# BMS_Master_RevB3.net
KiCad netlist of a schematic drawn in EAGLE
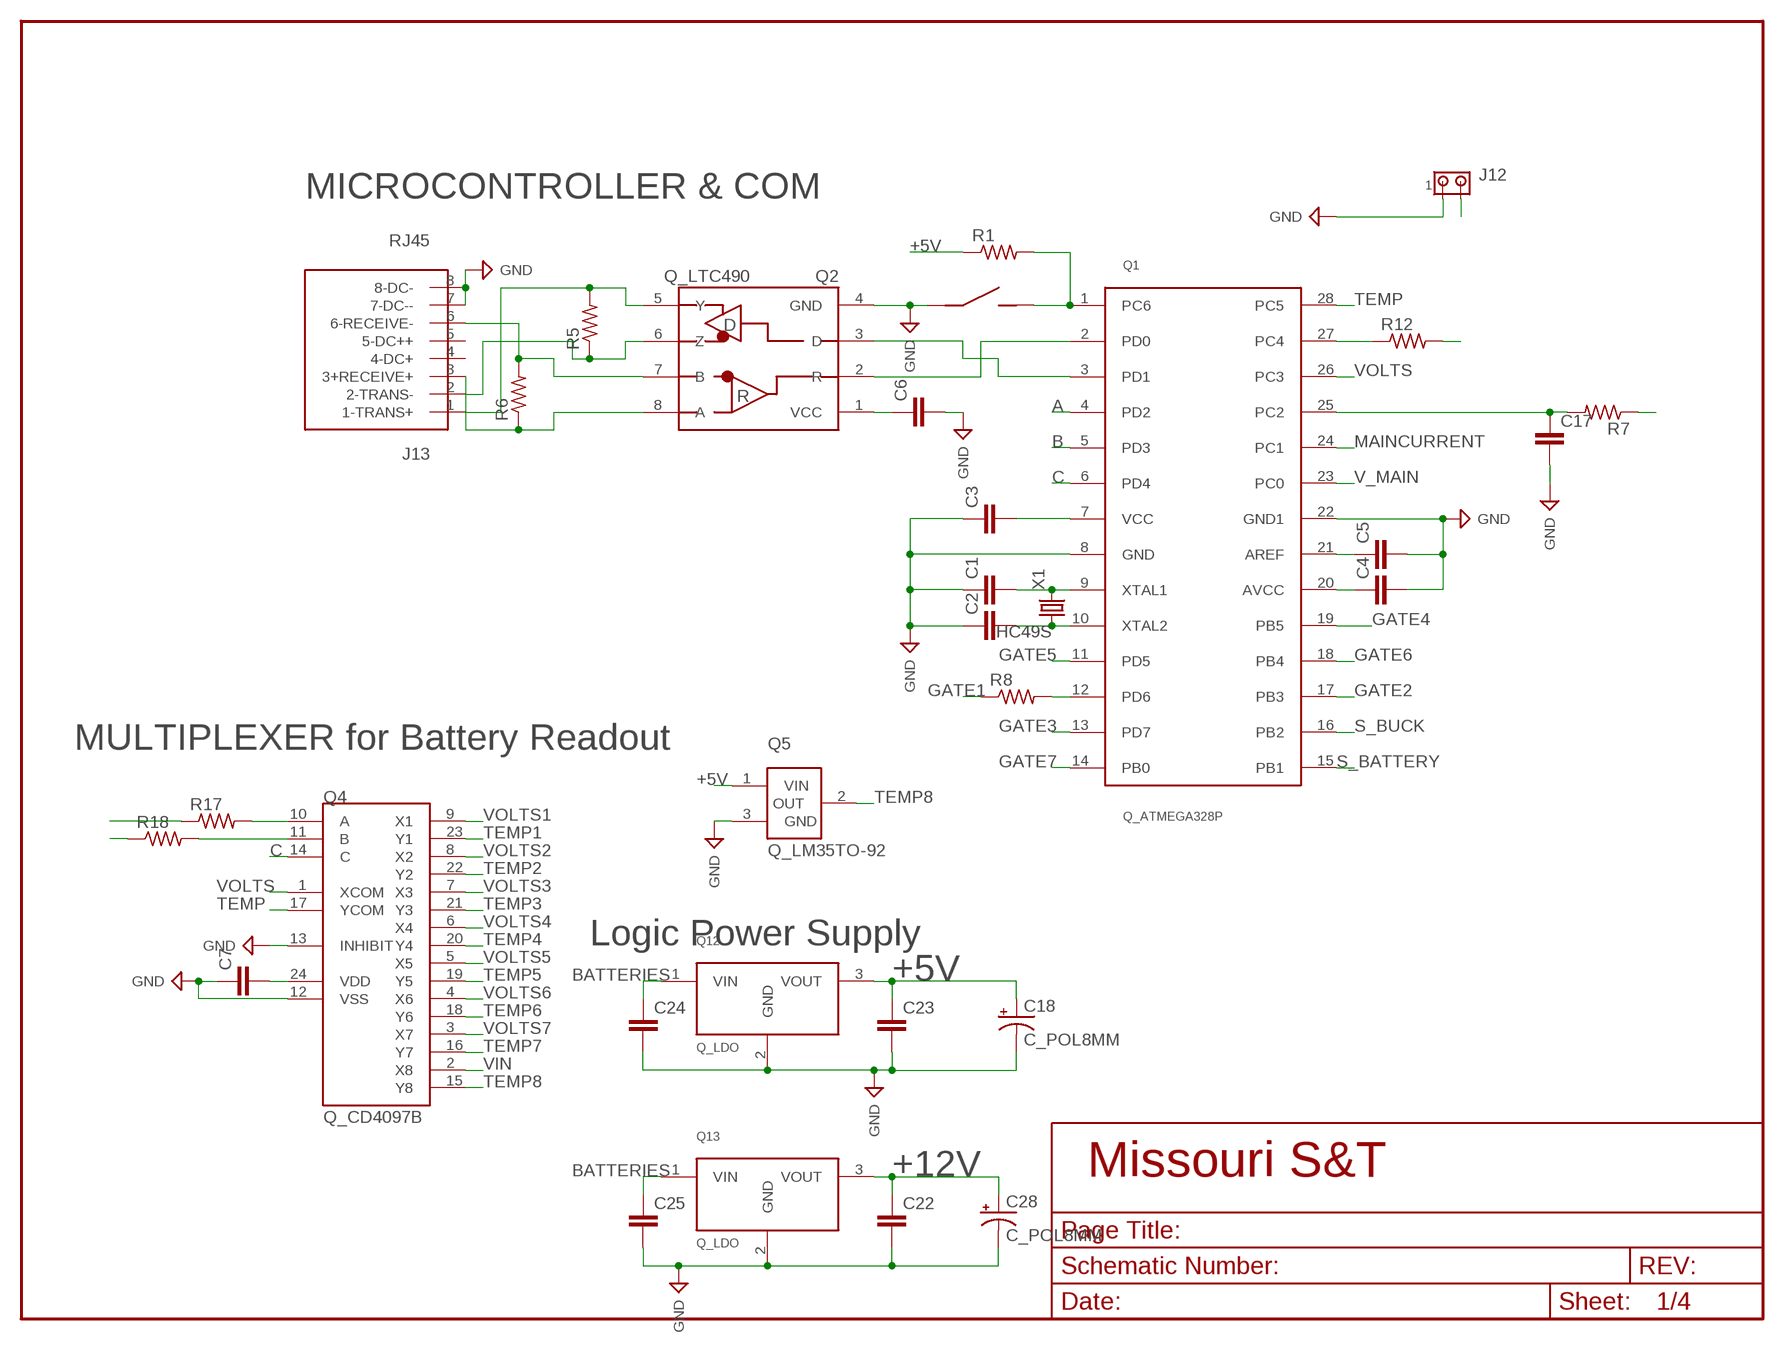
[diagram p0: schematic, sheet 1]
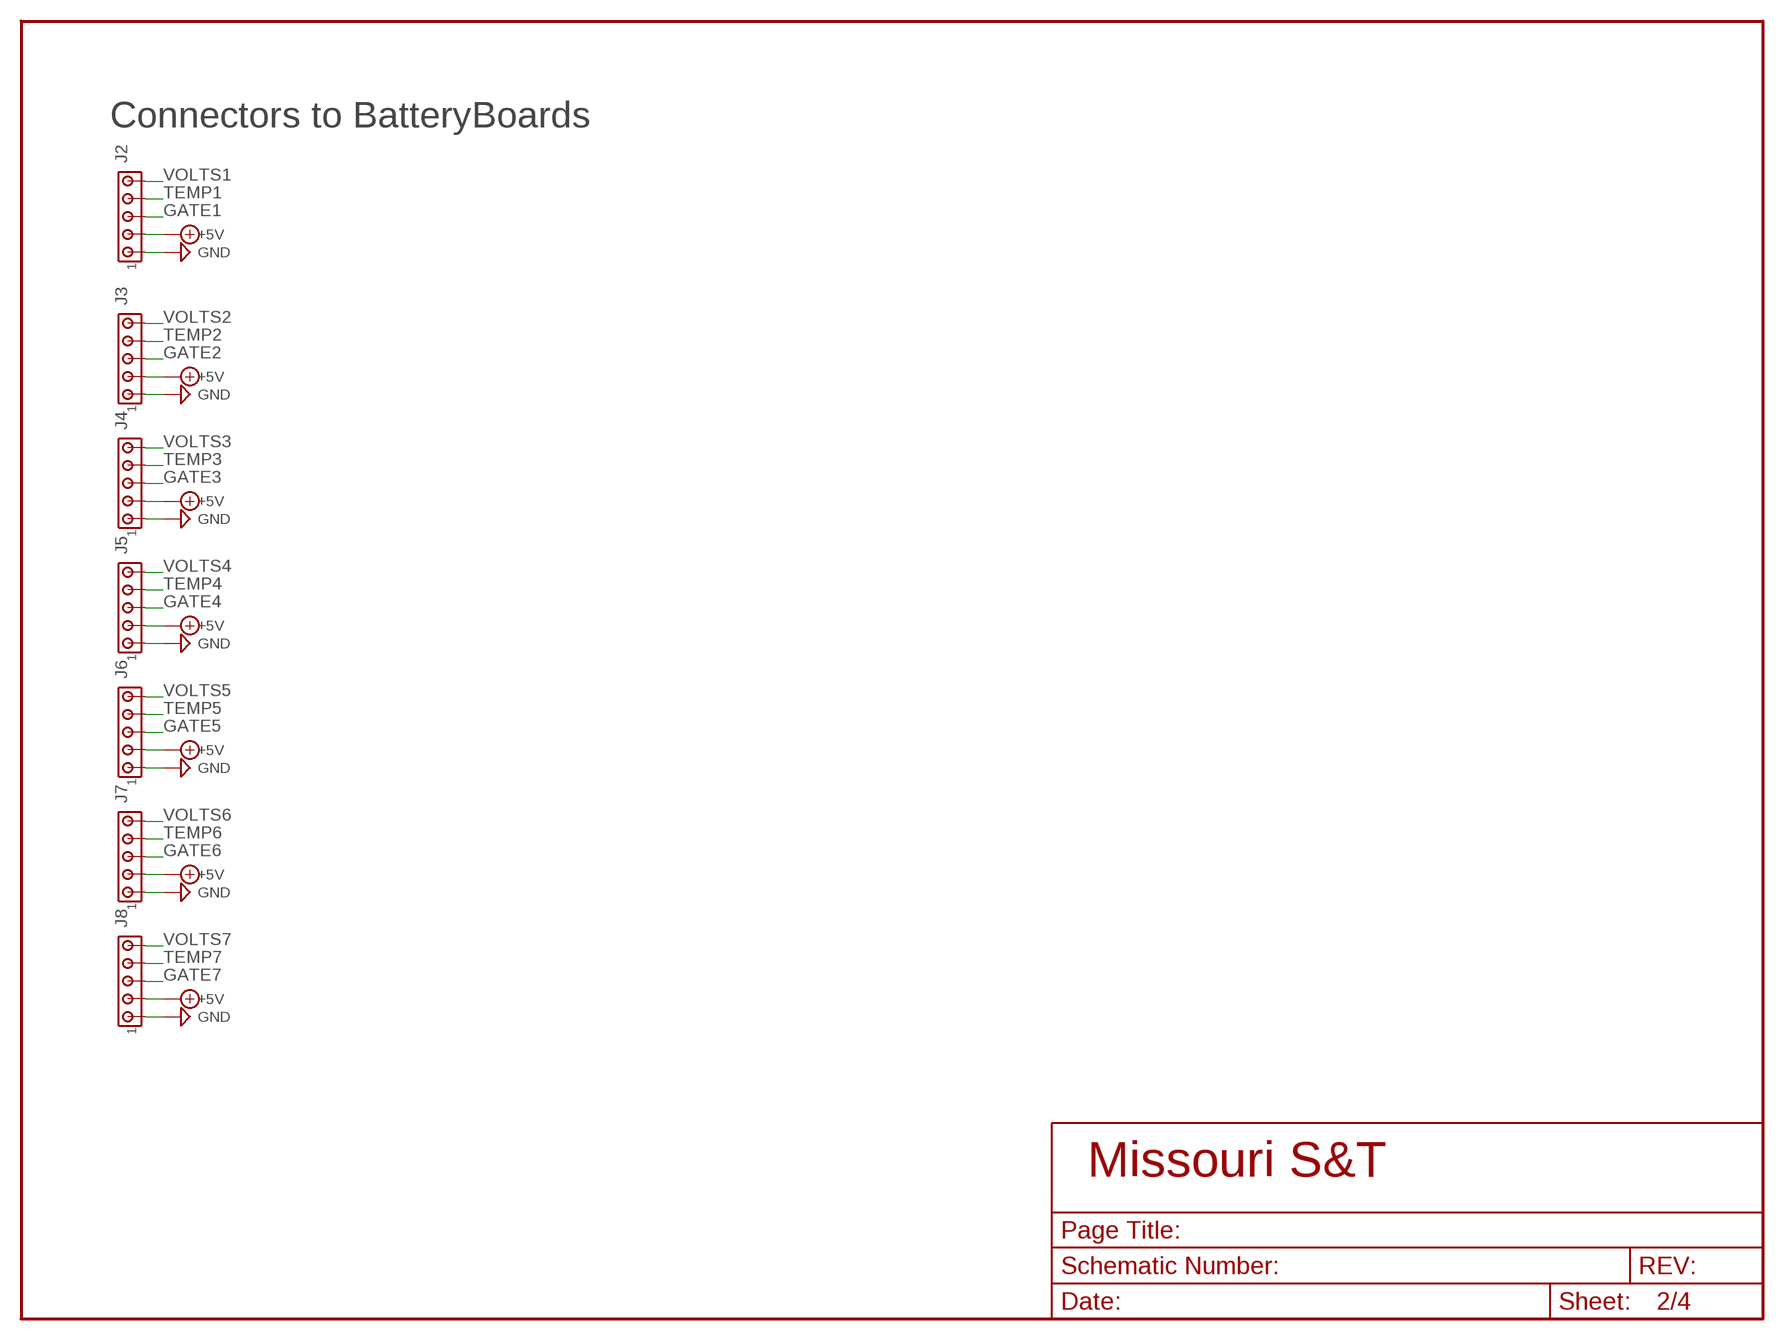
[diagram p1: schematic, sheet 2]
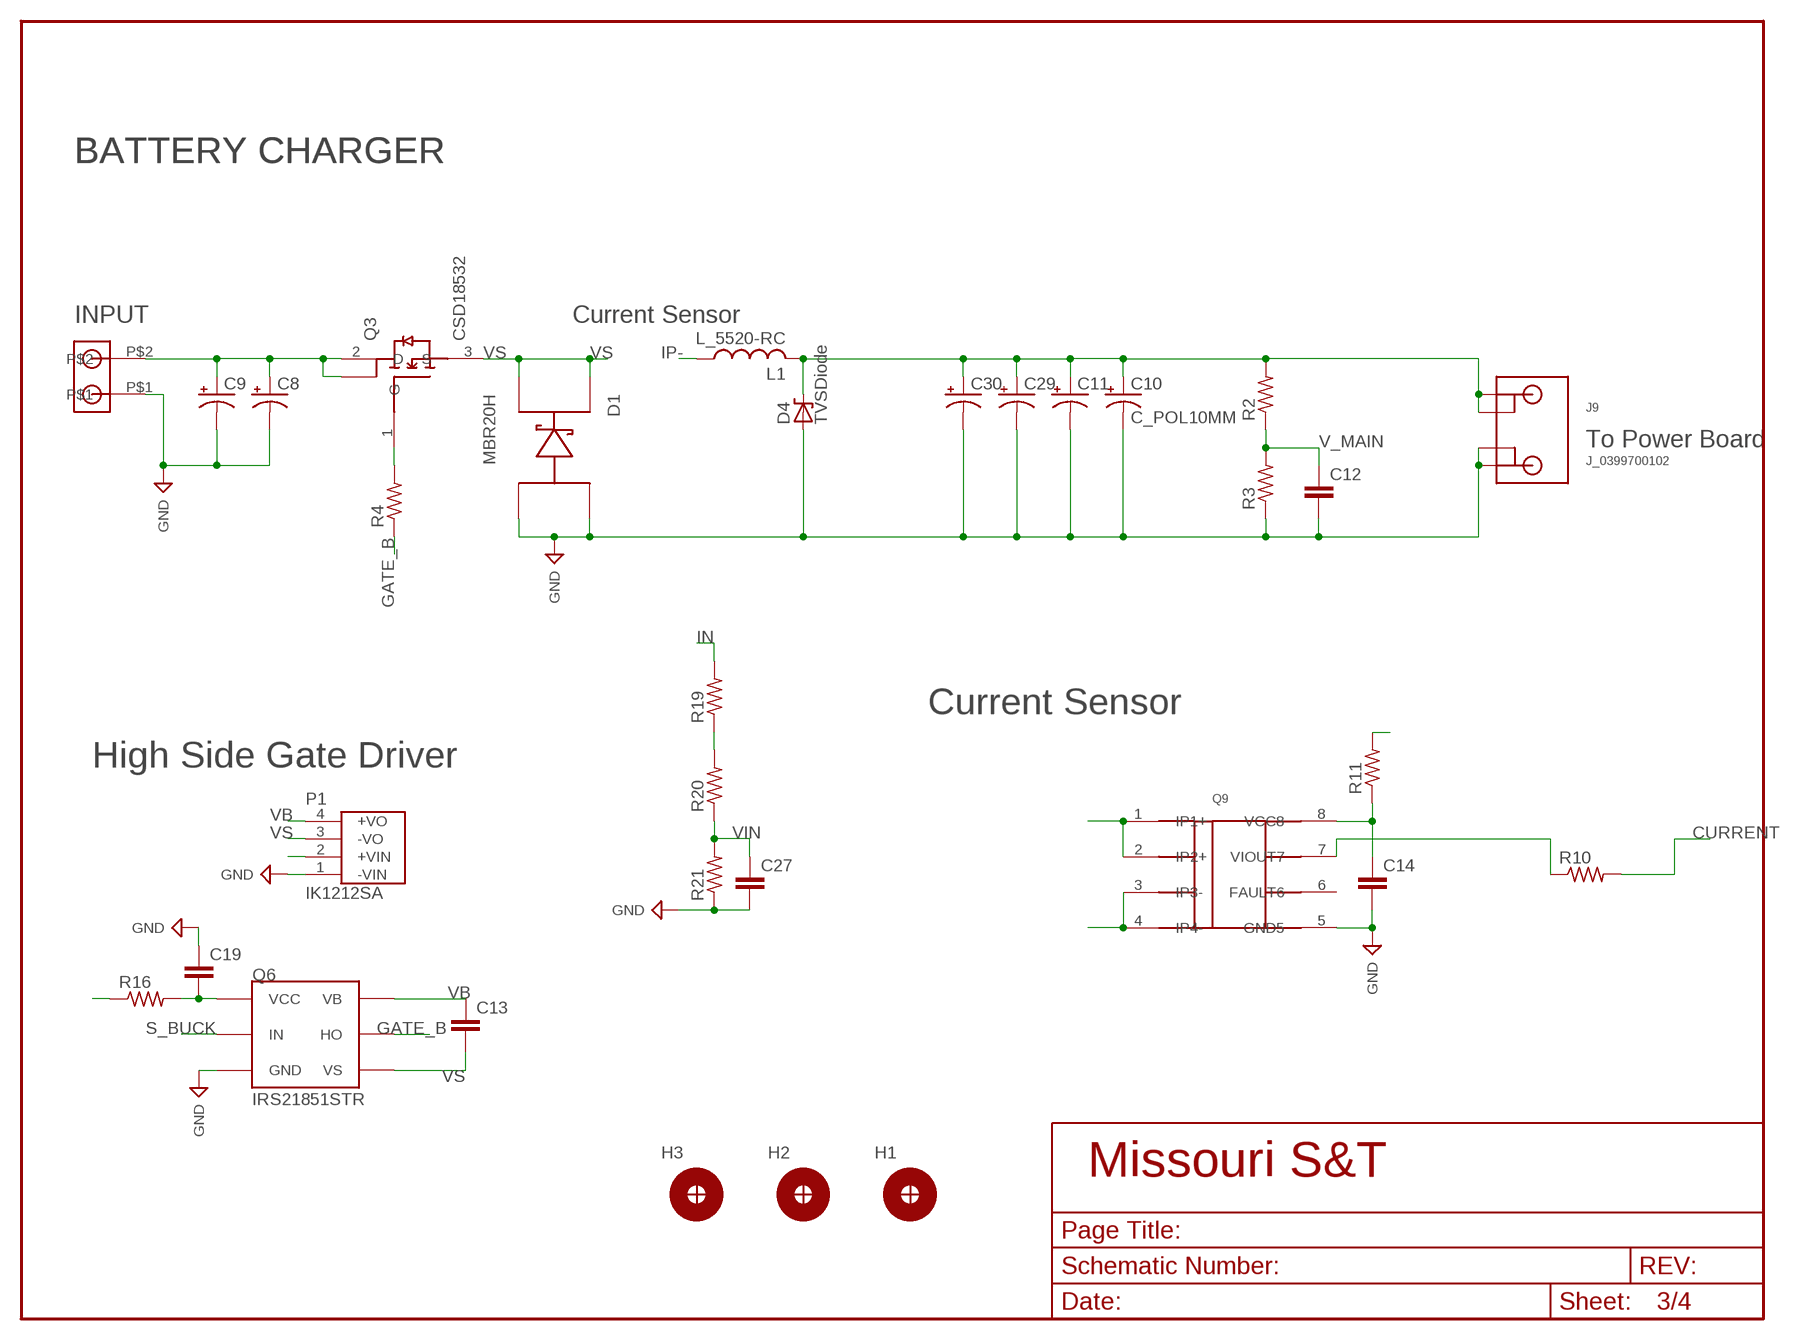
[diagram p2: schematic, sheet 3]
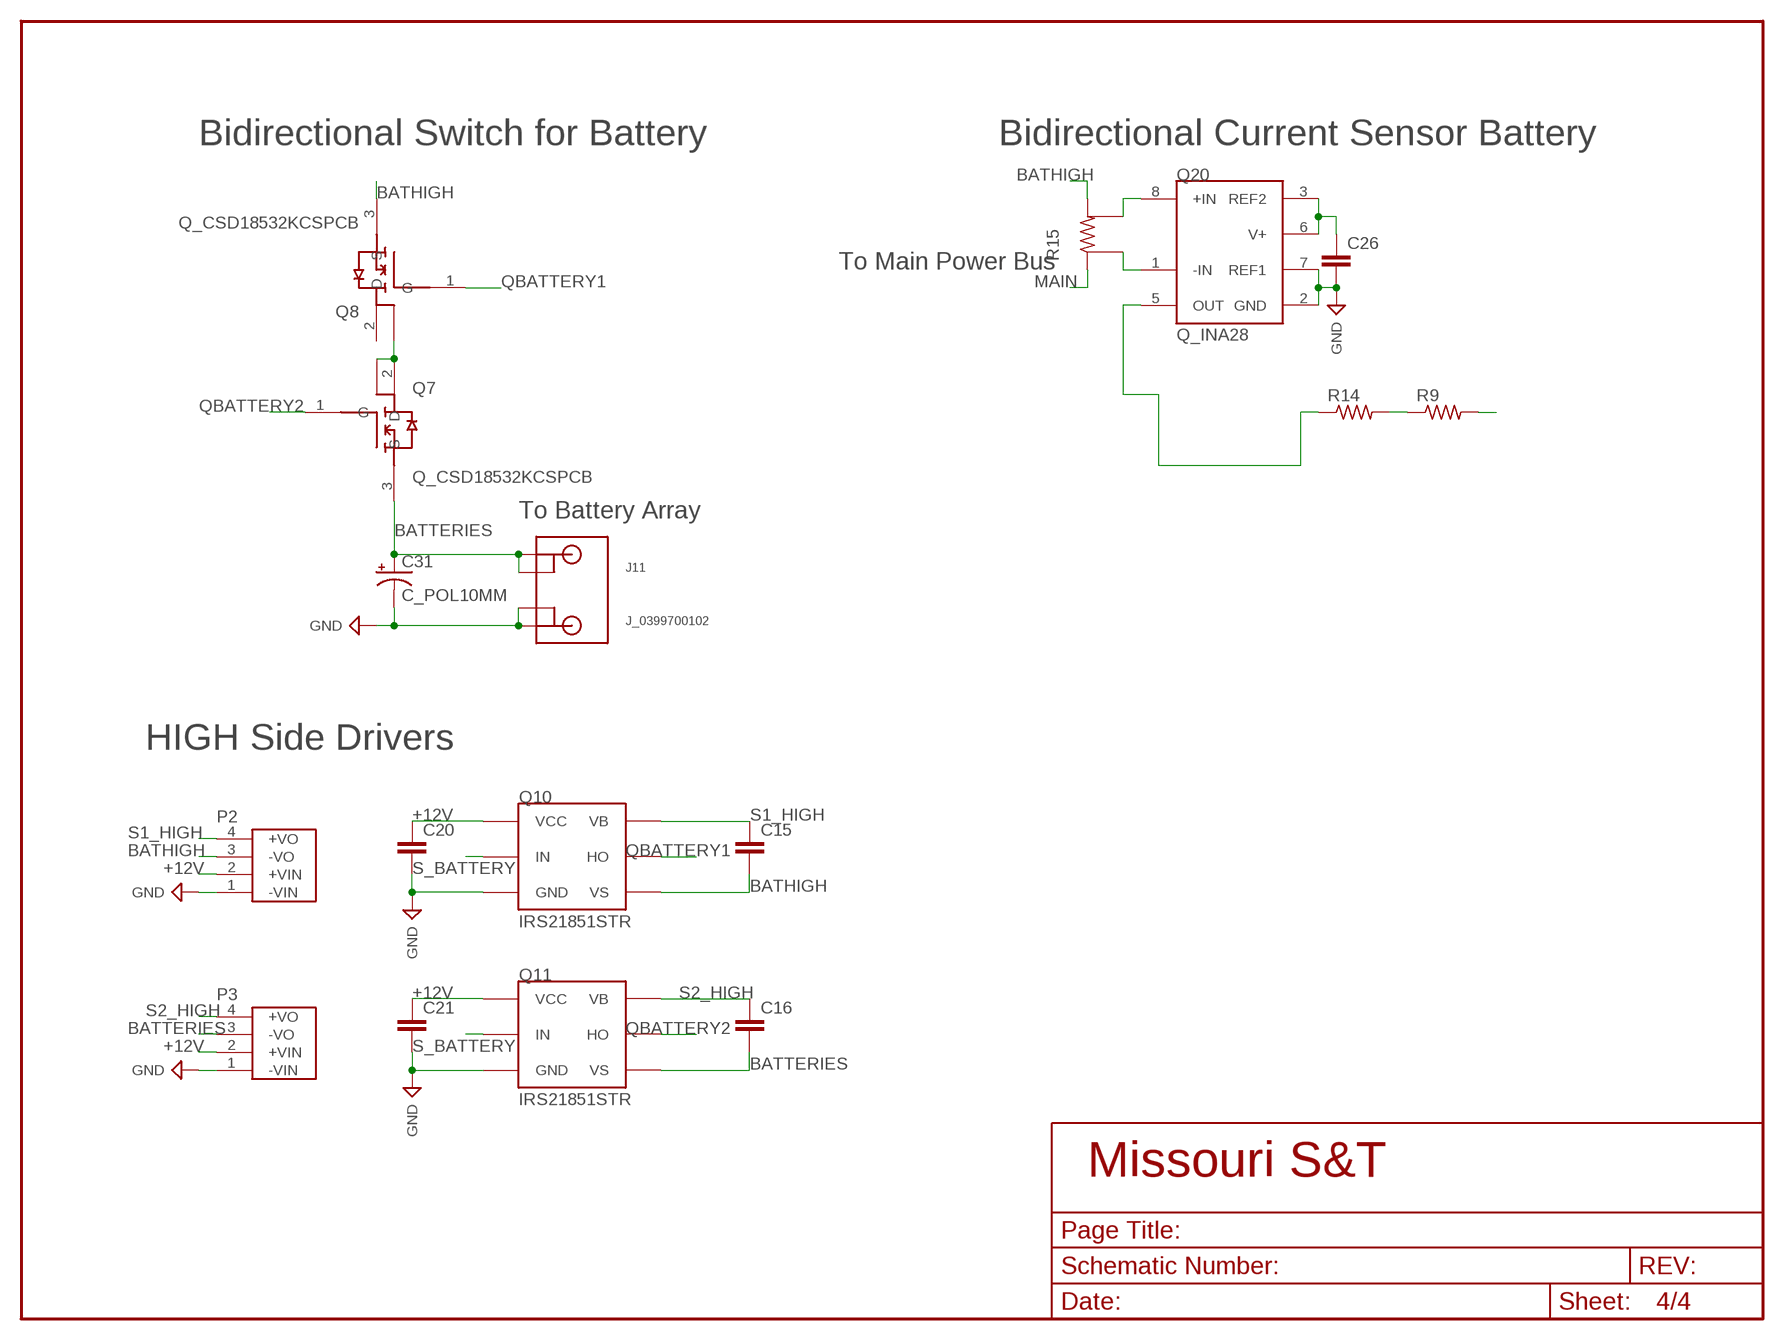
[diagram p3: schematic, sheet 4]

(export (version "E")
  (design (tool "Eeschema 10.0.6"))
  (components
    (comp (ref "J2")
      (value "J_MTA5P_100")
      (footprint "eagle-import:J_MTA100_5P")
      (libsource (lib "eagle-import") (part "J_MTA5P_100"))
    )
    (comp (ref "J3")
      (value "J_MTA5P_100")
      (footprint "eagle-import:J_MTA100_5P")
      (libsource (lib "eagle-import") (part "J_MTA5P_100"))
    )
    (comp (ref "J4")
      (value "J_MTA5P_100")
      (footprint "eagle-import:J_MTA100_5P")
      (libsource (lib "eagle-import") (part "J_MTA5P_100"))
    )
    (comp (ref "J5")
      (value "J_MTA5P_100")
      (footprint "eagle-import:J_MTA100_5P")
      (libsource (lib "eagle-import") (part "J_MTA5P_100"))
    )
    (comp (ref "J6")
      (value "J_MTA5P_100")
      (footprint "eagle-import:J_MTA100_5P")
      (libsource (lib "eagle-import") (part "J_MTA5P_100"))
    )
    (comp (ref "J7")
      (value "J_MTA5P_100")
      (footprint "eagle-import:J_MTA100_5P")
      (libsource (lib "eagle-import") (part "J_MTA5P_100"))
    )
    (comp (ref "J8")
      (value "J_MTA5P_100")
      (footprint "eagle-import:J_MTA100_5P")
      (libsource (lib "eagle-import") (part "J_MTA5P_100"))
    )
    (comp (ref "C15")
      (value "C_CAP_1206")
      (footprint "eagle-import:C_1206")
      (libsource (lib "eagle-import") (part "C_CAP_1206"))
    )
    (comp (ref "C16")
      (value "C_CAP_1206")
      (footprint "eagle-import:C_1206")
      (libsource (lib "eagle-import") (part "C_CAP_1206"))
    )
    (comp (ref "C20")
      (value "C_CAP_1206")
      (footprint "eagle-import:C_1206")
      (libsource (lib "eagle-import") (part "C_CAP_1206"))
    )
    (comp (ref "C21")
      (value "C_CAP_1206")
      (footprint "eagle-import:C_1206")
      (libsource (lib "eagle-import") (part "C_CAP_1206"))
    )
    (comp (ref "C26")
      (value "C_CAP_1206")
      (footprint "eagle-import:C_1206")
      (libsource (lib "eagle-import") (part "C_CAP_1206"))
    )
    (comp (ref "C31")
      (value "C_POL10MM")
      (footprint "eagle-import:C_10MM")
      (libsource (lib "eagle-import") (part "C_POL10MM"))
    )
    (comp (ref "J11")
      (value "J_0399700102")
      (footprint "eagle-import:J_2CONHC")
      (libsource (lib "eagle-import") (part "J_0399700102"))
    )
    (comp (ref "P2")
      (value "TME1215S")
      (footprint "eagle-import:TME1215S")
      (libsource (lib "eagle-import") (part "TME1215S"))
    )
    (comp (ref "P3")
      (value "TME1215S")
      (footprint "eagle-import:TME1215S")
      (libsource (lib "eagle-import") (part "TME1215S"))
    )
    (comp (ref "Q7")
      (value "Q_CSD18532KCSPCB")
      (footprint "eagle-import:TO-220-FLAT")
      (libsource (lib "eagle-import") (part "Q_CSD18532KCSPCB"))
    )
    (comp (ref "Q8")
      (value "Q_CSD18532KCSPCB")
      (footprint "eagle-import:TO-220-FLAT")
      (libsource (lib "eagle-import") (part "Q_CSD18532KCSPCB"))
    )
    (comp (ref "Q10")
      (value "IRS21851STR")
      (footprint "eagle-import:SOIC8")
      (libsource (lib "eagle-import") (part "Q_IRS21851STR"))
    )
    (comp (ref "Q11")
      (value "IRS21851STR")
      (footprint "eagle-import:SOIC8")
      (libsource (lib "eagle-import") (part "Q_IRS21851STR"))
    )
    (comp (ref "Q20")
      (value "Q_INA28")
      (footprint "eagle-import:SOIC8")
      (libsource (lib "eagle-import") (part "Q_INA28"))
    )
    (comp (ref "R9")
      (value "R_1/4W")
      (footprint "eagle-import:R_1_4W")
      (libsource (lib "eagle-import") (part "R_1/4W"))
    )
    (comp (ref "R14")
      (value "R_1/4W")
      (footprint "eagle-import:R_1_4W")
      (libsource (lib "eagle-import") (part "R_1/4W"))
    )
    (comp (ref "R15")
      (value "R_FC4L110R001JER")
      (footprint "eagle-import:R_FC4L")
      (libsource (lib "eagle-import") (part "R_FC4L110R001JER"))
    )
    (comp (ref "C1")
      (value "C_CAP_1206")
      (footprint "eagle-import:C_1206")
      (libsource (lib "eagle-import") (part "C_CAP_1206"))
    )
    (comp (ref "C2")
      (value "C_CAP_1206")
      (footprint "eagle-import:C_1206")
      (libsource (lib "eagle-import") (part "C_CAP_1206"))
    )
    (comp (ref "C3")
      (value "C_CAP_1206")
      (footprint "eagle-import:C_1206")
      (libsource (lib "eagle-import") (part "C_CAP_1206"))
    )
    (comp (ref "C4")
      (value "C_CAP_1206")
      (footprint "eagle-import:C_1206")
      (libsource (lib "eagle-import") (part "C_CAP_1206"))
    )
    (comp (ref "C5")
      (value "C_CAP_1206")
      (footprint "eagle-import:C_1206")
      (libsource (lib "eagle-import") (part "C_CAP_1206"))
    )
    (comp (ref "C6")
      (value "C_CAP_1206")
      (footprint "eagle-import:C_1206")
      (libsource (lib "eagle-import") (part "C_CAP_1206"))
    )
    (comp (ref "C7")
      (value "C_CAP_1206")
      (footprint "eagle-import:C_1206")
      (libsource (lib "eagle-import") (part "C_CAP_1206"))
    )
    (comp (ref "C17")
      (value "C_CAP_1206")
      (footprint "eagle-import:C_1206")
      (libsource (lib "eagle-import") (part "C_CAP_1206"))
    )
    (comp (ref "C18")
      (value "C_POL8MM")
      (footprint "eagle-import:C_8MM")
      (libsource (lib "eagle-import") (part "C_POL8MM"))
    )
    (comp (ref "C22")
      (value "C_CAP_1206")
      (footprint "eagle-import:C_1206")
      (libsource (lib "eagle-import") (part "C_CAP_1206"))
    )
    (comp (ref "C23")
      (value "C_CAP_1206")
      (footprint "eagle-import:C_1206")
      (libsource (lib "eagle-import") (part "C_CAP_1206"))
    )
    (comp (ref "C24")
      (value "C_CAP_1206")
      (footprint "eagle-import:C_1206")
      (libsource (lib "eagle-import") (part "C_CAP_1206"))
    )
    (comp (ref "C25")
      (value "C_CAP_1206")
      (footprint "eagle-import:C_1206")
      (libsource (lib "eagle-import") (part "C_CAP_1206"))
    )
    (comp (ref "C28")
      (value "C_POL8MM")
      (footprint "eagle-import:C_8MM")
      (libsource (lib "eagle-import") (part "C_POL8MM"))
    )
    (comp (ref "J1")
      (value "J_MC32857")
      (footprint "eagle-import:J_TOGGLE")
      (libsource (lib "eagle-import") (part "J_MC32857"))
    )
    (comp (ref "J12")
      (value "J_MTA2P_100")
      (footprint "eagle-import:J_MTA100_2P")
      (libsource (lib "eagle-import") (part "J_MTA2P_100"))
    )
    (comp (ref "J13")
      (value "RJ45")
      (footprint "eagle-import:RJ45-CAT5E")
      (libsource (lib "eagle-import") (part "RJ45"))
    )
    (comp (ref "Q1")
      (value "Q_ATMEGA328P")
      (footprint "eagle-import:DIP28")
      (libsource (lib "eagle-import") (part "Q_ATMEGA328P"))
    )
    (comp (ref "Q2")
      (value "Q_LTC490")
      (footprint "eagle-import:DIP8")
      (libsource (lib "eagle-import") (part "Q_LTC490"))
    )
    (comp (ref "Q4")
      (value "Q_CD4097B")
      (footprint "eagle-import:WDIP24")
      (libsource (lib "eagle-import") (part "Q_CD4067BRIGHT"))
    )
    (comp (ref "Q5")
      (value "Q_LM35TO-92")
      (footprint "eagle-import:TO-92-3")
      (libsource (lib "eagle-import") (part "Q_LM35TO-92"))
    )
    (comp (ref "Q12")
      (value "Q_LDO")
      (footprint "eagle-import:TO-220")
      (libsource (lib "eagle-import") (part "Q_LDO"))
    )
    (comp (ref "Q13")
      (value "Q_LDO")
      (footprint "eagle-import:TO-220")
      (libsource (lib "eagle-import") (part "Q_LDO"))
    )
    (comp (ref "R1")
      (value "R_RES_1206")
      (footprint "eagle-import:R_1206")
      (libsource (lib "eagle-import") (part "R_RES_1206"))
    )
    (comp (ref "R5")
      (value "R_RES_1206")
      (footprint "eagle-import:R_1206")
      (libsource (lib "eagle-import") (part "Lib_Passive - Copy_R_RES_1206"))
    )
    (comp (ref "R6")
      (value "R_RES_1206")
      (footprint "eagle-import:R_1206")
      (libsource (lib "eagle-import") (part "Lib_Passive - Copy_R_RES_1206"))
    )
    (comp (ref "R7")
      (value "R_1/4W")
      (footprint "eagle-import:R_1_4W")
      (libsource (lib "eagle-import") (part "R_1/4W"))
    )
    (comp (ref "R8")
      (value "R_1/4W")
      (footprint "eagle-import:R_1_4W")
      (libsource (lib "eagle-import") (part "R_1/4W"))
    )
    (comp (ref "R12")
      (value "R_RES_0805")
      (footprint "eagle-import:R_0805")
      (libsource (lib "eagle-import") (part "R_RES_0805"))
    )
    (comp (ref "R17")
      (value "R_1/4W")
      (footprint "eagle-import:R_1_4W")
      (libsource (lib "eagle-import") (part "R_1/4W"))
    )
    (comp (ref "R18")
      (value "R_1/4W")
      (footprint "eagle-import:R_1_4W")
      (libsource (lib "eagle-import") (part "R_1/4W"))
    )
    (comp (ref "X1")
      (value "HC49S")
      (footprint "eagle-import:HC-49")
      (libsource (lib "eagle-import") (part "X_HC49SCRYSTAL"))
    )
    (comp (ref "C8")
      (value "C_POL10MM")
      (footprint "eagle-import:C_10MM")
      (libsource (lib "eagle-import") (part "C_POL10MM"))
    )
    (comp (ref "C9")
      (value "C_POL10MM")
      (footprint "eagle-import:C_10MM")
      (libsource (lib "eagle-import") (part "C_POL10MM"))
    )
    (comp (ref "C10")
      (value "C_POL10MM")
      (footprint "eagle-import:C_10MM")
      (libsource (lib "eagle-import") (part "C_POL10MM"))
    )
    (comp (ref "C11")
      (value "C_POL10MM")
      (footprint "eagle-import:C_10MM")
      (libsource (lib "eagle-import") (part "C_POL10MM"))
    )
    (comp (ref "C12")
      (value "C_CAP_1206")
      (footprint "eagle-import:C_1206")
      (libsource (lib "eagle-import") (part "C_CAP_1206"))
    )
    (comp (ref "C13")
      (value "C_CAP_1206")
      (footprint "eagle-import:C_1206")
      (libsource (lib "eagle-import") (part "C_CAP_1206"))
    )
    (comp (ref "C14")
      (value "C_CAP_1206")
      (footprint "eagle-import:C_1206")
      (libsource (lib "eagle-import") (part "C_CAP_1206"))
    )
    (comp (ref "C19")
      (value "C_CAP_1206")
      (footprint "eagle-import:C_1206")
      (libsource (lib "eagle-import") (part "C_CAP_1206"))
    )
    (comp (ref "C27")
      (value "C_CAP_1206")
      (footprint "eagle-import:C_1206")
      (libsource (lib "eagle-import") (part "C_CAP_1206"))
    )
    (comp (ref "C29")
      (value "C_POL10MM")
      (footprint "eagle-import:C_10MM")
      (libsource (lib "eagle-import") (part "C_POL10MM"))
    )
    (comp (ref "C30")
      (value "C_POL10MM")
      (footprint "eagle-import:C_10MM")
      (libsource (lib "eagle-import") (part "C_POL10MM"))
    )
    (comp (ref "D1")
      (value "MBR20H")
      (footprint "eagle-import:TO-220-FLAT")
      (libsource (lib "eagle-import") (part "D_MBR20H150CTG"))
    )
    (comp (ref "D4")
      (value "TVSDiode")
      (footprint "eagle-import:DIODE_D3.5MM_LS15.24MM")
      (libsource (lib "eagle-import") (part "D_1.5KE480A_D3.5MM_LS15.24MM"))
    )
    (comp (ref "H1")
      (value "H_MNTHOLE_#6")
      (footprint "eagle-import:H_MNTHOLE_#6")
      (libsource (lib "eagle-import") (part "H_MNTHOLE_#6"))
    )
    (comp (ref "H2")
      (value "H_MNTHOLE_#6")
      (footprint "eagle-import:H_MNTHOLE_#6")
      (libsource (lib "eagle-import") (part "H_MNTHOLE_#6"))
    )
    (comp (ref "H3")
      (value "H_MNTHOLE_#6")
      (footprint "eagle-import:H_MNTHOLE_#6")
      (libsource (lib "eagle-import") (part "H_MNTHOLE_#6"))
    )
    (comp (ref "J9")
      (value "J_0399700102")
      (footprint "eagle-import:J_2CONHC")
      (libsource (lib "eagle-import") (part "J_0399700102"))
    )
    (comp (ref "J10")
      (value "J_1546074-2")
      (footprint "eagle-import:THERM_BLOCK_2")
      (libsource (lib "eagle-import") (part "J_1546074-2"))
    )
    (comp (ref "L1")
      (value "L_5520-RC")
      (footprint "eagle-import:L_5520-RC")
      (libsource (lib "eagle-import") (part "L_5520-RC"))
    )
    (comp (ref "P1")
      (value "IK1212SA")
      (footprint "eagle-import:TME1215S")
      (libsource (lib "eagle-import") (part "TME1215S"))
    )
    (comp (ref "Q3")
      (value "CSD18532")
      (footprint "eagle-import:TO-220-FLAT")
      (libsource (lib "eagle-import") (part "Q_CSD18532KCSPCB"))
    )
    (comp (ref "Q6")
      (value "IRS21851STR")
      (footprint "eagle-import:SOIC8")
      (libsource (lib "eagle-import") (part "Q_IRS21851STR"))
    )
    (comp (ref "Q9")
      (value "Q_SO8ACS711")
      (footprint "eagle-import:Q_SO8")
      (libsource (lib "eagle-import") (part "Q_SO8ACS711"))
    )
    (comp (ref "R2")
      (value "R_1/4W")
      (footprint "eagle-import:R_1_4W")
      (libsource (lib "eagle-import") (part "R_1/4W"))
    )
    (comp (ref "R3")
      (value "R_RES_1206")
      (footprint "eagle-import:R_1206")
      (libsource (lib "eagle-import") (part "R_RES_1206"))
    )
    (comp (ref "R4")
      (value "R_RES_1206")
      (footprint "eagle-import:R_1206")
      (libsource (lib "eagle-import") (part "Lib_Passive - Copy_R_RES_1206"))
    )
    (comp (ref "R10")
      (value "R_1/4W")
      (footprint "eagle-import:R_1_4W")
      (libsource (lib "eagle-import") (part "R_1/4W"))
    )
    (comp (ref "R11")
      (value "R_1/4W")
      (footprint "eagle-import:R_1_4W")
      (libsource (lib "eagle-import") (part "R_1/4W"))
    )
    (comp (ref "R16")
      (value "R_1/4W")
      (footprint "eagle-import:R_1_4W")
      (libsource (lib "eagle-import") (part "R_1/4W"))
    )
    (comp (ref "R19")
      (value "R_1/4W")
      (footprint "eagle-import:R_1_4W")
      (libsource (lib "eagle-import") (part "R_1/4W"))
    )
    (comp (ref "R20")
      (value "R_1/4W")
      (footprint "eagle-import:R_1_4W")
      (libsource (lib "eagle-import") (part "R_1/4W"))
    )
    (comp (ref "R21")
      (value "R_RES_1206")
      (footprint "eagle-import:R_1206")
      (libsource (lib "eagle-import") (part "R_RES_1206"))
    )
  )
  (nets
    (net (code "1") (name "+5V") (class "Default")
      (node (ref "C18") (pin "+") (pinfunction "+_+") (pintype "passive"))
      (node (ref "C23") (pin "1") (pinfunction "1_1") (pintype "passive"))
      (node (ref "C3") (pin "2") (pinfunction "2_2") (pintype "passive"))
      (node (ref "C4") (pin "1") (pinfunction "1_1") (pintype "passive"))
      (node (ref "C6") (pin "1") (pinfunction "1_1") (pintype "passive"))
      (node (ref "C7") (pin "2") (pinfunction "2_2") (pintype "passive"))
      (node (ref "J2") (pin "2") (pinfunction "2_2") (pintype "passive"))
      (node (ref "J3") (pin "2") (pinfunction "2_2") (pintype "passive"))
      (node (ref "J4") (pin "2") (pinfunction "2_2") (pintype "passive"))
      (node (ref "J5") (pin "2") (pinfunction "2_2") (pintype "passive"))
      (node (ref "J6") (pin "2") (pinfunction "2_2") (pintype "passive"))
      (node (ref "J7") (pin "2") (pinfunction "2_2") (pintype "passive"))
      (node (ref "J8") (pin "2") (pinfunction "2_2") (pintype "passive"))
      (node (ref "Q1") (pin "20") (pinfunction "AVCC_20") (pintype "bidirectional"))
      (node (ref "Q1") (pin "7") (pinfunction "VCC_7") (pintype "bidirectional"))
      (node (ref "Q12") (pin "3") (pinfunction "VOUT_3") (pintype "bidirectional"))
      (node (ref "Q2") (pin "1") (pinfunction "VCC_1") (pintype "bidirectional"))
      (node (ref "Q4") (pin "24") (pinfunction "VDD_24") (pintype "bidirectional"))
      (node (ref "Q5") (pin "1") (pinfunction "VIN_1") (pintype "bidirectional"))
      (node (ref "R1") (pin "1") (pinfunction "1_1") (pintype "passive"))
      (node (ref "R11") (pin "2") (pinfunction "2_2") (pintype "passive"))
      (node (ref "R12") (pin "2") (pinfunction "2_2") (pintype "passive"))
    )
    (net (code "2") (name "+5V1") (class "Default")
      (node (ref "C14") (pin "1") (pinfunction "1_1") (pintype "passive"))
      (node (ref "C26") (pin "1") (pinfunction "1_1") (pintype "passive"))
      (node (ref "Q20") (pin "3") (pinfunction "REF2_3") (pintype "bidirectional"))
      (node (ref "Q20") (pin "6") (pinfunction "V+_6") (pintype "bidirectional"))
      (node (ref "Q9") (pin "8") (pinfunction "VCC8_8") (pintype "bidirectional"))
      (node (ref "R11") (pin "1") (pinfunction "1_1") (pintype "passive"))
    )
    (net (code "3") (name "+12V") (class "Default")
      (node (ref "C20") (pin "1") (pinfunction "1_1") (pintype "passive"))
      (node (ref "C21") (pin "1") (pinfunction "1_1") (pintype "passive"))
      (node (ref "C22") (pin "1") (pinfunction "1_1") (pintype "passive"))
      (node (ref "C28") (pin "+") (pinfunction "+_+") (pintype "passive"))
      (node (ref "P2") (pin "2") (pinfunction "+VIN_2") (pintype "input"))
      (node (ref "P3") (pin "2") (pinfunction "+VIN_2") (pintype "input"))
      (node (ref "Q10") (pin "1") (pinfunction "VCC_1") (pintype "bidirectional"))
      (node (ref "Q11") (pin "1") (pinfunction "VCC_1") (pintype "bidirectional"))
      (node (ref "Q13") (pin "3") (pinfunction "VOUT_3") (pintype "bidirectional"))
      (node (ref "R16") (pin "1") (pinfunction "1_1") (pintype "passive"))
    )
    (net (code "4") (name "+12V1") (class "Default")
      (node (ref "C19") (pin "2") (pinfunction "2_2") (pintype "passive"))
      (node (ref "P1") (pin "2") (pinfunction "+VIN_2") (pintype "input"))
      (node (ref "Q6") (pin "1") (pinfunction "VCC_1") (pintype "bidirectional"))
      (node (ref "R16") (pin "2") (pinfunction "2_2") (pintype "passive"))
    )
    (net (code "5") (name "A") (class "Default")
      (node (ref "Q1") (pin "4") (pinfunction "PD2_4") (pintype "bidirectional"))
      (node (ref "R17") (pin "1") (pinfunction "1_1") (pintype "passive"))
    )
    (net (code "6") (name "B") (class "Default")
      (node (ref "Q1") (pin "5") (pinfunction "PD3_5") (pintype "bidirectional"))
      (node (ref "R18") (pin "1") (pinfunction "1_1") (pintype "passive"))
    )
    (net (code "7") (name "BATHIGH") (class "Default")
      (node (ref "C15") (pin "2") (pinfunction "2_2") (pintype "passive"))
      (node (ref "P2") (pin "3") (pinfunction "-VO_3") (pintype "output"))
      (node (ref "Q10") (pin "6") (pinfunction "VS_6") (pintype "bidirectional"))
      (node (ref "Q8") (pin "3") (pinfunction "S_3") (pintype "bidirectional"))
      (node (ref "R15") (pin "2") (pinfunction "2_2") (pintype "passive"))
    )
    (net (code "8") (name "BATTERIES") (class "Default")
      (node (ref "C16") (pin "2") (pinfunction "2_2") (pintype "passive"))
      (node (ref "C24") (pin "1") (pinfunction "1_1") (pintype "passive"))
      (node (ref "C25") (pin "1") (pinfunction "1_1") (pintype "passive"))
      (node (ref "C31") (pin "P$1") (pinfunction "+_P$1") (pintype "passive"))
      (node (ref "J11") (pin "PIN1-1") (pinfunction "1-1_PIN1-1") (pintype "bidirectional"))
      (node (ref "J11") (pin "PIN1-2") (pinfunction "1-2_PIN1-2") (pintype "bidirectional"))
      (node (ref "P3") (pin "3") (pinfunction "-VO_3") (pintype "output"))
      (node (ref "Q11") (pin "6") (pinfunction "VS_6") (pintype "bidirectional"))
      (node (ref "Q12") (pin "1") (pinfunction "VIN_1") (pintype "bidirectional"))
      (node (ref "Q13") (pin "1") (pinfunction "VIN_1") (pintype "bidirectional"))
      (node (ref "Q7") (pin "3") (pinfunction "S_3") (pintype "bidirectional"))
    )
    (net (code "9") (name "C") (class "Default")
      (node (ref "Q1") (pin "6") (pinfunction "PD4_6") (pintype "bidirectional"))
      (node (ref "Q4") (pin "14") (pinfunction "C_14") (pintype "bidirectional"))
    )
    (net (code "10") (name "CURRENT") (class "Default")
      (node (ref "R10") (pin "2") (pinfunction "2_2") (pintype "passive"))
      (node (ref "R7") (pin "1") (pinfunction "1_1") (pintype "passive"))
    )
    (net (code "11") (name "GATE1") (class "Default")
      (node (ref "J2") (pin "3") (pinfunction "3_3") (pintype "passive"))
      (node (ref "R8") (pin "1") (pinfunction "1_1") (pintype "passive"))
    )
    (net (code "12") (name "GATE2") (class "Default")
      (node (ref "J3") (pin "3") (pinfunction "3_3") (pintype "passive"))
      (node (ref "Q1") (pin "17") (pinfunction "PB3_17") (pintype "bidirectional"))
    )
    (net (code "13") (name "GATE3") (class "Default")
      (node (ref "J4") (pin "3") (pinfunction "3_3") (pintype "passive"))
      (node (ref "Q1") (pin "13") (pinfunction "PD7_13") (pintype "bidirectional"))
    )
    (net (code "14") (name "GATE4") (class "Default")
      (node (ref "J5") (pin "3") (pinfunction "3_3") (pintype "passive"))
      (node (ref "Q1") (pin "19") (pinfunction "PB5_19") (pintype "bidirectional"))
    )
    (net (code "15") (name "GATE5") (class "Default")
      (node (ref "J6") (pin "3") (pinfunction "3_3") (pintype "passive"))
      (node (ref "Q1") (pin "11") (pinfunction "PD5_11") (pintype "bidirectional"))
    )
    (net (code "16") (name "GATE6") (class "Default")
      (node (ref "J7") (pin "3") (pinfunction "3_3") (pintype "passive"))
      (node (ref "Q1") (pin "18") (pinfunction "PB4_18") (pintype "bidirectional"))
    )
    (net (code "17") (name "GATE7") (class "Default")
      (node (ref "J8") (pin "3") (pinfunction "3_3") (pintype "passive"))
      (node (ref "Q1") (pin "14") (pinfunction "PB0_14") (pintype "bidirectional"))
    )
    (net (code "18") (name "GATE_B") (class "Default")
      (node (ref "Q6") (pin "7") (pinfunction "HO_7") (pintype "bidirectional"))
      (node (ref "R4") (pin "1") (pinfunction "1_1") (pintype "passive"))
    )
    (net (code "19") (name "GND") (class "Default")
      (node (ref "C1") (pin "1") (pinfunction "1_1") (pintype "passive"))
      (node (ref "C10") (pin "P$2") (pinfunction "-_P$2") (pintype "passive"))
      (node (ref "C11") (pin "P$2") (pinfunction "-_P$2") (pintype "passive"))
      (node (ref "C12") (pin "2") (pinfunction "2_2") (pintype "passive"))
      (node (ref "C14") (pin "2") (pinfunction "2_2") (pintype "passive"))
      (node (ref "C17") (pin "2") (pinfunction "2_2") (pintype "passive"))
      (node (ref "C18") (pin "-") (pinfunction "-_-") (pintype "passive"))
      (node (ref "C19") (pin "1") (pinfunction "1_1") (pintype "passive"))
      (node (ref "C2") (pin "1") (pinfunction "1_1") (pintype "passive"))
      (node (ref "C20") (pin "2") (pinfunction "2_2") (pintype "passive"))
      (node (ref "C21") (pin "2") (pinfunction "2_2") (pintype "passive"))
      (node (ref "C22") (pin "2") (pinfunction "2_2") (pintype "passive"))
      (node (ref "C23") (pin "2") (pinfunction "2_2") (pintype "passive"))
      (node (ref "C24") (pin "2") (pinfunction "2_2") (pintype "passive"))
      (node (ref "C25") (pin "2") (pinfunction "2_2") (pintype "passive"))
      (node (ref "C26") (pin "2") (pinfunction "2_2") (pintype "passive"))
      (node (ref "C27") (pin "2") (pinfunction "2_2") (pintype "passive"))
      (node (ref "C28") (pin "-") (pinfunction "-_-") (pintype "passive"))
      (node (ref "C29") (pin "P$2") (pinfunction "-_P$2") (pintype "passive"))
      (node (ref "C3") (pin "1") (pinfunction "1_1") (pintype "passive"))
      (node (ref "C30") (pin "P$2") (pinfunction "-_P$2") (pintype "passive"))
      (node (ref "C31") (pin "P$2") (pinfunction "-_P$2") (pintype "passive"))
      (node (ref "C4") (pin "2") (pinfunction "2_2") (pintype "passive"))
      (node (ref "C5") (pin "2") (pinfunction "2_2") (pintype "passive"))
      (node (ref "C6") (pin "2") (pinfunction "2_2") (pintype "passive"))
      (node (ref "C7") (pin "1") (pinfunction "1_1") (pintype "passive"))
      (node (ref "C8") (pin "P$2") (pinfunction "-_P$2") (pintype "passive"))
      (node (ref "C9") (pin "P$2") (pinfunction "-_P$2") (pintype "passive"))
      (node (ref "D1") (pin "1") (pinfunction "A1_1") (pintype "bidirectional"))
      (node (ref "D1") (pin "3") (pinfunction "A2_3") (pintype "bidirectional"))
      (node (ref "D4") (pin "A") (pinfunction "A_A") (pintype "passive"))
      (node (ref "J1") (pin "P$1") (pinfunction "1_P$1") (pintype "bidirectional"))
      (node (ref "J10") (pin "P$1") (pinfunction "P$1_P$1") (pintype "bidirectional"))
      (node (ref "J11") (pin "PIN2-1") (pinfunction "2-1_PIN2-1") (pintype "bidirectional"))
      (node (ref "J11") (pin "PIN2-2") (pinfunction "2-2_PIN2-2") (pintype "bidirectional"))
      (node (ref "J12") (pin "1") (pinfunction "1_1") (pintype "passive"))
      (node (ref "J13") (pin "7") (pinfunction "7-DC--_7") (pintype "bidirectional"))
      (node (ref "J13") (pin "8") (pinfunction "8-DC-_8") (pintype "bidirectional"))
      (node (ref "J2") (pin "1") (pinfunction "1_1") (pintype "passive"))
      (node (ref "J3") (pin "1") (pinfunction "1_1") (pintype "passive"))
      (node (ref "J4") (pin "1") (pinfunction "1_1") (pintype "passive"))
      (node (ref "J5") (pin "1") (pinfunction "1_1") (pintype "passive"))
      (node (ref "J6") (pin "1") (pinfunction "1_1") (pintype "passive"))
      (node (ref "J7") (pin "1") (pinfunction "1_1") (pintype "passive"))
      (node (ref "J8") (pin "1") (pinfunction "1_1") (pintype "passive"))
      (node (ref "J9") (pin "PIN2-1") (pinfunction "2-1_PIN2-1") (pintype "bidirectional"))
      (node (ref "J9") (pin "PIN2-2") (pinfunction "2-2_PIN2-2") (pintype "bidirectional"))
      (node (ref "P1") (pin "1") (pinfunction "-VIN_1") (pintype "input"))
      (node (ref "P2") (pin "1") (pinfunction "-VIN_1") (pintype "input"))
      (node (ref "P3") (pin "1") (pinfunction "-VIN_1") (pintype "input"))
      (node (ref "Q1") (pin "22") (pinfunction "GND1_22") (pintype "bidirectional"))
      (node (ref "Q1") (pin "8") (pinfunction "GND_8") (pintype "bidirectional"))
      (node (ref "Q10") (pin "4") (pinfunction "GND_4") (pintype "bidirectional"))
      (node (ref "Q11") (pin "4") (pinfunction "GND_4") (pintype "bidirectional"))
      (node (ref "Q12") (pin "2") (pinfunction "GND_2") (pintype "bidirectional"))
      (node (ref "Q13") (pin "2") (pinfunction "GND_2") (pintype "bidirectional"))
      (node (ref "Q2") (pin "4") (pinfunction "GND_4") (pintype "bidirectional"))
      (node (ref "Q20") (pin "2") (pinfunction "GND_2") (pintype "bidirectional"))
      (node (ref "Q20") (pin "7") (pinfunction "REF1_7") (pintype "bidirectional"))
      (node (ref "Q4") (pin "12") (pinfunction "VSS_12") (pintype "bidirectional"))
      (node (ref "Q4") (pin "13") (pinfunction "INHIBIT_13") (pintype "bidirectional"))
      (node (ref "Q5") (pin "3") (pinfunction "GND_3") (pintype "bidirectional"))
      (node (ref "Q6") (pin "4") (pinfunction "GND_4") (pintype "bidirectional"))
      (node (ref "Q9") (pin "5") (pinfunction "GND5_5") (pintype "bidirectional"))
      (node (ref "R21") (pin "1") (pinfunction "1_1") (pintype "passive"))
      (node (ref "R3") (pin "1") (pinfunction "1_1") (pintype "passive"))
    )
    (net (code "20") (name "IN") (class "Default")
      (node (ref "C8") (pin "P$1") (pinfunction "+_P$1") (pintype "passive"))
      (node (ref "C9") (pin "P$1") (pinfunction "+_P$1") (pintype "passive"))
      (node (ref "J10") (pin "P$2") (pinfunction "P$2_P$2") (pintype "bidirectional"))
      (node (ref "Q3") (pin "2") (pinfunction "D_2") (pintype "bidirectional"))
      (node (ref "Q3") (pin "4") (pinfunction "P$1_4") (pintype "bidirectional"))
      (node (ref "R19") (pin "2") (pinfunction "2_2") (pintype "passive"))
    )
    (net (code "21") (name "IP-") (class "Default")
      (node (ref "L1") (pin "1") (pinfunction "1_1") (pintype "passive"))
      (node (ref "Q9") (pin "1") (pinfunction "IP1+_1") (pintype "bidirectional"))
      (node (ref "Q9") (pin "2") (pinfunction "IP2+_2") (pintype "bidirectional"))
    )
    (net (code "22") (name "MAIN") (class "Default")
      (node (ref "C10") (pin "P$1") (pinfunction "+_P$1") (pintype "passive"))
      (node (ref "C11") (pin "P$1") (pinfunction "+_P$1") (pintype "passive"))
      (node (ref "C29") (pin "P$1") (pinfunction "+_P$1") (pintype "passive"))
      (node (ref "C30") (pin "P$1") (pinfunction "+_P$1") (pintype "passive"))
      (node (ref "D4") (pin "C") (pinfunction "K_C") (pintype "passive"))
      (node (ref "J9") (pin "PIN1-1") (pinfunction "1-1_PIN1-1") (pintype "bidirectional"))
      (node (ref "J9") (pin "PIN1-2") (pinfunction "1-2_PIN1-2") (pintype "bidirectional"))
      (node (ref "L1") (pin "2") (pinfunction "2_2") (pintype "passive"))
      (node (ref "R15") (pin "1") (pinfunction "1_1") (pintype "passive"))
      (node (ref "R2") (pin "2") (pinfunction "2_2") (pintype "passive"))
    )
    (net (code "23") (name "MAINCURRENT") (class "Default")
      (node (ref "Q1") (pin "24") (pinfunction "PC1_24") (pintype "bidirectional"))
      (node (ref "R9") (pin "2") (pinfunction "2_2") (pintype "passive"))
    )
    (net (code "24") (name "Net-(J1-2)") (class "Default")
      (node (ref "J1") (pin "P$2") (pinfunction "2_P$2") (pintype "bidirectional"))
      (node (ref "Q1") (pin "1") (pinfunction "PC6_1") (pintype "bidirectional"))
      (node (ref "R1") (pin "2") (pinfunction "2_2") (pintype "passive"))
    )
    (net (code "25") (name "Net-(J13-1-TRANS+)") (class "Default")
      (node (ref "J13") (pin "1") (pinfunction "1-TRANS+_1") (pintype "bidirectional"))
      (node (ref "Q2") (pin "5") (pinfunction "Y_5") (pintype "bidirectional"))
      (node (ref "R5") (pin "2") (pinfunction "2_2") (pintype "passive"))
    )
    (net (code "26") (name "Net-(J13-2-TRANS-)") (class "Default")
      (node (ref "J13") (pin "2") (pinfunction "2-TRANS-_2") (pintype "bidirectional"))
      (node (ref "Q2") (pin "6") (pinfunction "Z_6") (pintype "bidirectional"))
      (node (ref "R5") (pin "1") (pinfunction "1_1") (pintype "passive"))
    )
    (net (code "27") (name "Net-(J13-3+RECEIVE+)") (class "Default")
      (node (ref "J13") (pin "3") (pinfunction "3+RECEIVE+_3") (pintype "bidirectional"))
      (node (ref "Q2") (pin "8") (pinfunction "A_8") (pintype "bidirectional"))
      (node (ref "R6") (pin "1") (pinfunction "1_1") (pintype "passive"))
    )
    (net (code "28") (name "Net-(J13-6-RECEIVE-)") (class "Default")
      (node (ref "J13") (pin "6") (pinfunction "6-RECEIVE-_6") (pintype "bidirectional"))
      (node (ref "Q2") (pin "7") (pinfunction "B_7") (pintype "bidirectional"))
      (node (ref "R6") (pin "2") (pinfunction "2_2") (pintype "passive"))
    )
    (net (code "29") (name "Net-(Q1-AREF)") (class "Default")
      (node (ref "C5") (pin "1") (pinfunction "1_1") (pintype "passive"))
      (node (ref "Q1") (pin "21") (pinfunction "AREF_21") (pintype "bidirectional"))
    )
    (net (code "30") (name "Net-(Q1-PC2)") (class "Default")
      (node (ref "C17") (pin "1") (pinfunction "1_1") (pintype "passive"))
      (node (ref "Q1") (pin "25") (pinfunction "PC2_25") (pintype "bidirectional"))
      (node (ref "R7") (pin "2") (pinfunction "2_2") (pintype "passive"))
    )
    (net (code "31") (name "Net-(Q1-PD0)") (class "Default")
      (node (ref "Q1") (pin "2") (pinfunction "PD0_2") (pintype "bidirectional"))
      (node (ref "Q2") (pin "2") (pinfunction "R_2") (pintype "bidirectional"))
    )
    (net (code "32") (name "Net-(Q1-PD1)") (class "Default")
      (node (ref "Q1") (pin "3") (pinfunction "PD1_3") (pintype "bidirectional"))
      (node (ref "Q2") (pin "3") (pinfunction "D_3") (pintype "bidirectional"))
    )
    (net (code "33") (name "Net-(Q1-PD6)") (class "Default")
      (node (ref "Q1") (pin "12") (pinfunction "PD6_12") (pintype "bidirectional"))
      (node (ref "R8") (pin "2") (pinfunction "2_2") (pintype "passive"))
    )
    (net (code "34") (name "Net-(Q1-XTAL1)") (class "Default")
      (node (ref "C1") (pin "2") (pinfunction "2_2") (pintype "passive"))
      (node (ref "Q1") (pin "9") (pinfunction "XTAL1_9") (pintype "bidirectional"))
      (node (ref "X1") (pin "P$2") (pinfunction "2_P$2") (pintype "passive"))
    )
    (net (code "35") (name "Net-(Q1-XTAL2)") (class "Default")
      (node (ref "C2") (pin "2") (pinfunction "2_2") (pintype "passive"))
      (node (ref "Q1") (pin "10") (pinfunction "XTAL2_10") (pintype "bidirectional"))
      (node (ref "X1") (pin "P$1") (pinfunction "1_P$1") (pintype "passive"))
    )
    (net (code "36") (name "Net-(Q3-G)") (class "Default")
      (node (ref "Q3") (pin "1") (pinfunction "G_1") (pintype "bidirectional"))
      (node (ref "R4") (pin "2") (pinfunction "2_2") (pintype "passive"))
    )
    (net (code "37") (name "Net-(Q4-A)") (class "Default")
      (node (ref "Q4") (pin "10") (pinfunction "A_10") (pintype "bidirectional"))
      (node (ref "R17") (pin "2") (pinfunction "2_2") (pintype "passive"))
    )
    (net (code "38") (name "Net-(Q4-B)") (class "Default")
      (node (ref "Q4") (pin "11") (pinfunction "B_11") (pintype "bidirectional"))
      (node (ref "R18") (pin "2") (pinfunction "2_2") (pintype "passive"))
    )
    (net (code "39") (name "Net-(Q7-D)") (class "Default")
      (node (ref "Q7") (pin "2") (pinfunction "D_2") (pintype "bidirectional"))
      (node (ref "Q7") (pin "4") (pinfunction "P$1_4") (pintype "bidirectional"))
      (node (ref "Q8") (pin "4") (pinfunction "P$1_4") (pintype "bidirectional"))
    )
    (net (code "40") (name "Net-(Q9-VIOUT7)") (class "Default")
      (node (ref "Q9") (pin "7") (pinfunction "VIOUT7_7") (pintype "bidirectional"))
      (node (ref "R10") (pin "1") (pinfunction "1_1") (pintype "passive"))
    )
    (net (code "41") (name "Net-(Q20-+IN)") (class "Default")
      (node (ref "Q20") (pin "8") (pinfunction "+IN_8") (pintype "bidirectional"))
      (node (ref "R15") (pin "SENSE2") (pinfunction "SENSE2_SENSE2") (pintype "bidirectional"))
    )
    (net (code "42") (name "Net-(Q20--IN)") (class "Default")
      (node (ref "Q20") (pin "1") (pinfunction "-IN_1") (pintype "bidirectional"))
      (node (ref "R15") (pin "SENSE1") (pinfunction "SENSE1_SENSE1") (pintype "bidirectional"))
    )
    (net (code "43") (name "Net-(Q20-OUT)") (class "Default")
      (node (ref "Q20") (pin "5") (pinfunction "OUT_5") (pintype "bidirectional"))
      (node (ref "R14") (pin "1") (pinfunction "1_1") (pintype "passive"))
    )
    (net (code "44") (name "Net-(R14-Pad2)") (class "Default")
      (node (ref "R14") (pin "2") (pinfunction "2_2") (pintype "passive"))
      (node (ref "R9") (pin "1") (pinfunction "1_1") (pintype "passive"))
    )
    (net (code "45") (name "Net-(R19-Pad1)") (class "Default")
      (node (ref "R19") (pin "1") (pinfunction "1_1") (pintype "passive"))
      (node (ref "R20") (pin "2") (pinfunction "2_2") (pintype "passive"))
    )
    (net (code "46") (name "PANIC") (class "Default")
      (node (ref "J12") (pin "2") (pinfunction "2_2") (pintype "passive"))
      (node (ref "Q1") (pin "27") (pinfunction "PC4_27") (pintype "bidirectional"))
      (node (ref "R12") (pin "1") (pinfunction "1_1") (pintype "passive"))
    )
    (net (code "47") (name "QBATTERY1") (class "Default")
      (node (ref "Q10") (pin "7") (pinfunction "HO_7") (pintype "bidirectional"))
      (node (ref "Q8") (pin "1") (pinfunction "G_1") (pintype "bidirectional"))
    )
    (net (code "48") (name "QBATTERY2") (class "Default")
      (node (ref "Q11") (pin "7") (pinfunction "HO_7") (pintype "bidirectional"))
      (node (ref "Q7") (pin "1") (pinfunction "G_1") (pintype "bidirectional"))
    )
    (net (code "49") (name "S1_HIGH") (class "Default")
      (node (ref "C15") (pin "1") (pinfunction "1_1") (pintype "passive"))
      (node (ref "P2") (pin "4") (pinfunction "+VO_4") (pintype "output"))
      (node (ref "Q10") (pin "8") (pinfunction "VB_8") (pintype "bidirectional"))
    )
    (net (code "50") (name "S2_HIGH") (class "Default")
      (node (ref "C16") (pin "1") (pinfunction "1_1") (pintype "passive"))
      (node (ref "P3") (pin "4") (pinfunction "+VO_4") (pintype "output"))
      (node (ref "Q11") (pin "8") (pinfunction "VB_8") (pintype "bidirectional"))
    )
    (net (code "51") (name "S_BATTERY") (class "Default")
      (node (ref "Q1") (pin "15") (pinfunction "PB1_15") (pintype "bidirectional"))
      (node (ref "Q10") (pin "2") (pinfunction "IN_2") (pintype "bidirectional"))
      (node (ref "Q11") (pin "2") (pinfunction "IN_2") (pintype "bidirectional"))
    )
    (net (code "52") (name "S_BUCK") (class "Default")
      (node (ref "Q1") (pin "16") (pinfunction "PB2_16") (pintype "bidirectional"))
      (node (ref "Q6") (pin "2") (pinfunction "IN_2") (pintype "bidirectional"))
    )
    (net (code "53") (name "TEMP") (class "Default")
      (node (ref "Q1") (pin "28") (pinfunction "PC5_28") (pintype "bidirectional"))
      (node (ref "Q4") (pin "17") (pinfunction "YCOM_17") (pintype "bidirectional"))
    )
    (net (code "54") (name "TEMP1") (class "Default")
      (node (ref "J2") (pin "4") (pinfunction "4_4") (pintype "passive"))
      (node (ref "Q4") (pin "23") (pinfunction "Y1_23") (pintype "bidirectional"))
    )
    (net (code "55") (name "TEMP2") (class "Default")
      (node (ref "J3") (pin "4") (pinfunction "4_4") (pintype "passive"))
      (node (ref "Q4") (pin "22") (pinfunction "Y2_22") (pintype "bidirectional"))
    )
    (net (code "56") (name "TEMP3") (class "Default")
      (node (ref "J4") (pin "4") (pinfunction "4_4") (pintype "passive"))
      (node (ref "Q4") (pin "21") (pinfunction "Y3_21") (pintype "bidirectional"))
    )
    (net (code "57") (name "TEMP4") (class "Default")
      (node (ref "J5") (pin "4") (pinfunction "4_4") (pintype "passive"))
      (node (ref "Q4") (pin "20") (pinfunction "Y4_20") (pintype "bidirectional"))
    )
    (net (code "58") (name "TEMP5") (class "Default")
      (node (ref "J6") (pin "4") (pinfunction "4_4") (pintype "passive"))
      (node (ref "Q4") (pin "19") (pinfunction "Y5_19") (pintype "bidirectional"))
    )
    (net (code "59") (name "TEMP6") (class "Default")
      (node (ref "J7") (pin "4") (pinfunction "4_4") (pintype "passive"))
      (node (ref "Q4") (pin "18") (pinfunction "Y6_18") (pintype "bidirectional"))
    )
    (net (code "60") (name "TEMP7") (class "Default")
      (node (ref "J8") (pin "4") (pinfunction "4_4") (pintype "passive"))
      (node (ref "Q4") (pin "16") (pinfunction "Y7_16") (pintype "bidirectional"))
    )
    (net (code "61") (name "TEMP8") (class "Default")
      (node (ref "Q4") (pin "15") (pinfunction "Y8_15") (pintype "bidirectional"))
      (node (ref "Q5") (pin "2") (pinfunction "OUT_2") (pintype "bidirectional"))
    )
    (net (code "62") (name "VB") (class "Default")
      (node (ref "C13") (pin "1") (pinfunction "1_1") (pintype "passive"))
      (node (ref "P1") (pin "4") (pinfunction "+VO_4") (pintype "output"))
      (node (ref "Q6") (pin "8") (pinfunction "VB_8") (pintype "bidirectional"))
    )
    (net (code "63") (name "VIN") (class "Default")
      (node (ref "C27") (pin "1") (pinfunction "1_1") (pintype "passive"))
      (node (ref "Q4") (pin "2") (pinfunction "X8_2") (pintype "bidirectional"))
      (node (ref "R20") (pin "1") (pinfunction "1_1") (pintype "passive"))
      (node (ref "R21") (pin "2") (pinfunction "2_2") (pintype "passive"))
    )
    (net (code "64") (name "VOLTS") (class "Default")
      (node (ref "Q1") (pin "26") (pinfunction "PC3_26") (pintype "bidirectional"))
      (node (ref "Q4") (pin "1") (pinfunction "XCOM_1") (pintype "bidirectional"))
    )
    (net (code "65") (name "VOLTS1") (class "Default")
      (node (ref "J2") (pin "5") (pinfunction "5_5") (pintype "passive"))
      (node (ref "Q4") (pin "9") (pinfunction "X1_9") (pintype "bidirectional"))
    )
    (net (code "66") (name "VOLTS2") (class "Default")
      (node (ref "J3") (pin "5") (pinfunction "5_5") (pintype "passive"))
      (node (ref "Q4") (pin "8") (pinfunction "X2_8") (pintype "bidirectional"))
    )
    (net (code "67") (name "VOLTS3") (class "Default")
      (node (ref "J4") (pin "5") (pinfunction "5_5") (pintype "passive"))
      (node (ref "Q4") (pin "7") (pinfunction "X3_7") (pintype "bidirectional"))
    )
    (net (code "68") (name "VOLTS4") (class "Default")
      (node (ref "J5") (pin "5") (pinfunction "5_5") (pintype "passive"))
      (node (ref "Q4") (pin "6") (pinfunction "X4_6") (pintype "bidirectional"))
    )
    (net (code "69") (name "VOLTS5") (class "Default")
      (node (ref "J6") (pin "5") (pinfunction "5_5") (pintype "passive"))
      (node (ref "Q4") (pin "5") (pinfunction "X5_5") (pintype "bidirectional"))
    )
    (net (code "70") (name "VOLTS6") (class "Default")
      (node (ref "J7") (pin "5") (pinfunction "5_5") (pintype "passive"))
      (node (ref "Q4") (pin "4") (pinfunction "X6_4") (pintype "bidirectional"))
    )
    (net (code "71") (name "VOLTS7") (class "Default")
      (node (ref "J8") (pin "5") (pinfunction "5_5") (pintype "passive"))
      (node (ref "Q4") (pin "3") (pinfunction "X7_3") (pintype "bidirectional"))
    )
    (net (code "72") (name "VS") (class "Default")
      (node (ref "C13") (pin "2") (pinfunction "2_2") (pintype "passive"))
      (node (ref "D1") (pin "2") (pinfunction "C1_2") (pintype "bidirectional"))
      (node (ref "D1") (pin "4") (pinfunction "C2_4") (pintype "bidirectional"))
      (node (ref "P1") (pin "3") (pinfunction "-VO_3") (pintype "output"))
      (node (ref "Q3") (pin "3") (pinfunction "S_3") (pintype "bidirectional"))
      (node (ref "Q6") (pin "6") (pinfunction "VS_6") (pintype "bidirectional"))
      (node (ref "Q9") (pin "3") (pinfunction "IP3-_3") (pintype "bidirectional"))
      (node (ref "Q9") (pin "4") (pinfunction "IP4-_4") (pintype "bidirectional"))
    )
    (net (code "73") (name "V_MAIN") (class "Default")
      (node (ref "C12") (pin "1") (pinfunction "1_1") (pintype "passive"))
      (node (ref "Q1") (pin "23") (pinfunction "PC0_23") (pintype "bidirectional"))
      (node (ref "R2") (pin "1") (pinfunction "1_1") (pintype "passive"))
      (node (ref "R3") (pin "2") (pinfunction "2_2") (pintype "passive"))
    )
    (net (code "74") (name "unconnected-(H1-Pad1)") (class "Default")
      (node (ref "H1") (pin "1") (pinfunction "1_1") (pintype "passive"))
    )
    (net (code "75") (name "unconnected-(H2-Pad1)") (class "Default")
      (node (ref "H2") (pin "1") (pinfunction "1_1") (pintype "passive"))
    )
    (net (code "76") (name "unconnected-(H3-Pad1)") (class "Default")
      (node (ref "H3") (pin "1") (pinfunction "1_1") (pintype "passive"))
    )
    (net (code "77") (name "unconnected-(J13-4-DC+-Pad4)") (class "Default")
      (node (ref "J13") (pin "4") (pinfunction "4-DC+_4") (pintype "bidirectional"))
    )
    (net (code "78") (name "unconnected-(J13-5-DC++-Pad5)") (class "Default")
      (node (ref "J13") (pin "5") (pinfunction "5-DC++_5") (pintype "bidirectional"))
    )
    (net (code "79") (name "unconnected-(Q8-D-Pad2)") (class "Default")
      (node (ref "Q8") (pin "2") (pinfunction "D_2") (pintype "bidirectional"))
    )
    (net (code "80") (name "unconnected-(Q9-FAULT6-Pad6)") (class "Default")
      (node (ref "Q9") (pin "6") (pinfunction "FAULT6_6") (pintype "bidirectional"))
    )
  )
)
